# RfLauchPadAdapter.net
KiCad netlist of a schematic drawn in Altium Designer
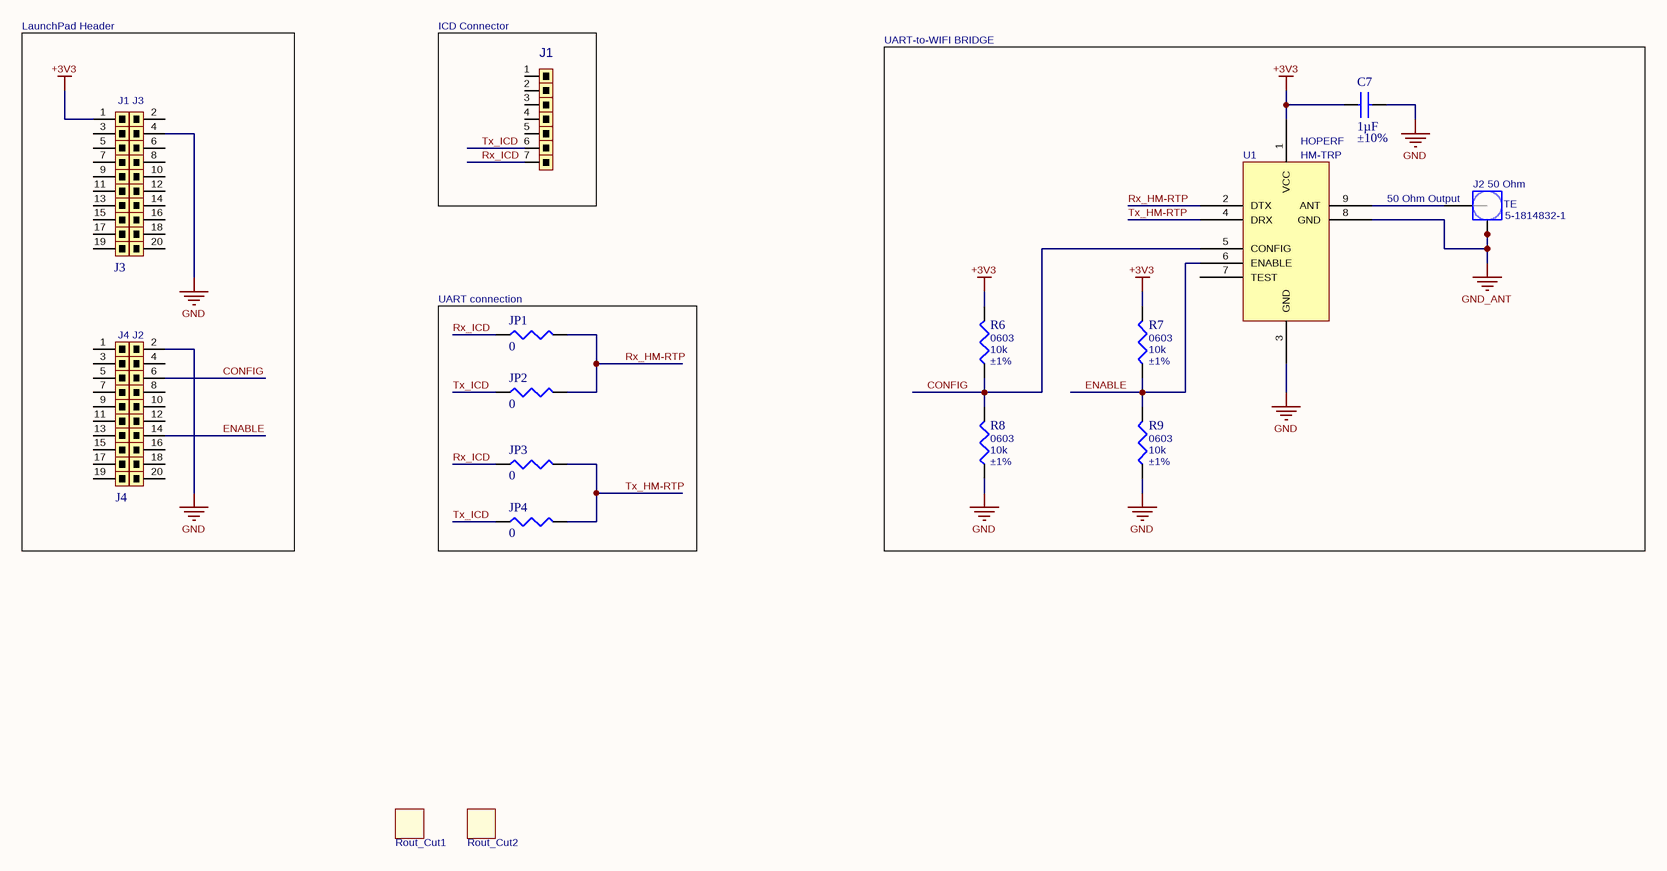
[diagram p0: RfLauchPadAdapter.SchDoc]

(export (version "E")
  (design (tool "Eeschema 10.0.6"))
  (components
    (comp (ref "C7")
      (value "GRM188R61C105KA93D")
      (footprint "C0603")
      (description "CAP CER 1UF 16V 10% X5R 0603")
      (fields
        (field (name "MANUFACTURER") "Murata Electronics North America")
        (field (name "CAPACITANCE") "1µF")
        (field (name "TOLERANCE") "±10%")
      )
      (libsource (lib "CAP") (part "GRM188R61C105KA93D"))
    )
    (comp (ref "J1")
      (value "Header 1x7")
      (footprint "Post Height Terminal Strip 1x7")
      (libsource (lib "CON_Standard") (part "Header 1x7"))
    )
    (comp (ref "J2")
      (value "5-1814832-1")
      (footprint "5-1814832-1")
      (description "CONN SMA JACK STR 50 OHM PCB")
      (fields (field (name "IMPEDANCE") "50 Ohm") (field (name "MANUFACTURER") "TE"))
      (libsource (lib "CON_TE") (part "5-1814832-1"))
    )
    (comp (ref "J3")
      (value "Header 2x10")
      (footprint "Post Height Terminal Strip 2x10")
      (libsource (lib "CON_Standard") (part "Header 2x10"))
    )
    (comp (ref "J4")
      (value "Header 2x10")
      (footprint "Post Height Terminal Strip 2x10")
      (libsource (lib "CON_Standard") (part "Header 2x10"))
    )
    (comp (ref "JP1")
      (value "ERJ-3GEY0R00V")
      (footprint "R0603")
      (description "0R JUMPER 1/10W")
      (fields
        (field (name "MANUFACTURER") "Panasonic Electronic Components")
        (field (name "RESISTANCE (OHMS)") "0")
      )
      (libsource (lib "RES") (part "ERJ-3GEY0R00V"))
    )
    (comp (ref "JP2")
      (value "ERJ-3GEY0R00V")
      (footprint "R0603")
      (description "0R JUMPER 1/10W")
      (fields
        (field (name "MANUFACTURER") "Panasonic Electronic Components")
        (field (name "RESISTANCE (OHMS)") "0")
      )
      (libsource (lib "RES") (part "ERJ-3GEY0R00V"))
    )
    (comp (ref "JP3")
      (value "ERJ-3GEY0R00V")
      (footprint "R0603")
      (description "0R JUMPER 1/10W")
      (fields
        (field (name "MANUFACTURER") "Panasonic Electronic Components")
        (field (name "RESISTANCE (OHMS)") "0")
      )
      (libsource (lib "RES") (part "ERJ-3GEY0R00V"))
    )
    (comp (ref "JP4")
      (value "ERJ-3GEY0R00V")
      (footprint "R0603")
      (description "0R JUMPER 1/10W")
      (fields
        (field (name "MANUFACTURER") "Panasonic Electronic Components")
        (field (name "RESISTANCE (OHMS)") "0")
      )
      (libsource (lib "RES") (part "ERJ-3GEY0R00V"))
    )
    (comp (ref "R6")
      (value "ERJ-3EKF1002V")
      (footprint "R0603")
      (description "10K OHM 1% 1/10W 0603")
      (fields
        (field (name "MANUFACTURER") "Panasonic Electronic Components")
        (field (name "SUPPLIER DEVICE PACKAGE") "0603")
        (field (name "RESISTANCE (OHMS)") "10k")
        (field (name "TOLERANCE") "±1%")
      )
      (libsource (lib "RES") (part "ERJ-3EKF1002V"))
    )
    (comp (ref "R7")
      (value "ERJ-3EKF1002V")
      (footprint "R0603")
      (description "10K OHM 1% 1/10W 0603")
      (fields
        (field (name "MANUFACTURER") "Panasonic Electronic Components")
        (field (name "SUPPLIER DEVICE PACKAGE") "0603")
        (field (name "RESISTANCE (OHMS)") "10k")
        (field (name "TOLERANCE") "±1%")
      )
      (libsource (lib "RES") (part "ERJ-3EKF1002V"))
    )
    (comp (ref "R8")
      (value "ERJ-3EKF1002V")
      (footprint "R0603")
      (description "10K OHM 1% 1/10W 0603")
      (fields
        (field (name "MANUFACTURER") "Panasonic Electronic Components")
        (field (name "SUPPLIER DEVICE PACKAGE") "0603")
        (field (name "RESISTANCE (OHMS)") "10k")
        (field (name "TOLERANCE") "±1%")
      )
      (libsource (lib "RES") (part "ERJ-3EKF1002V"))
    )
    (comp (ref "R9")
      (value "ERJ-3EKF1002V")
      (footprint "R0603")
      (description "10K OHM 1% 1/10W 0603")
      (fields
        (field (name "MANUFACTURER") "Panasonic Electronic Components")
        (field (name "SUPPLIER DEVICE PACKAGE") "0603")
        (field (name "RESISTANCE (OHMS)") "10k")
        (field (name "TOLERANCE") "±1%")
      )
      (libsource (lib "RES") (part "ERJ-3EKF1002V"))
    )
    (comp (ref "Rout_Cut1")
      (value "Rout_Cut")
      (footprint "RoutCut")
      (description "1.6mm")
      (libsource (lib "Misc") (part "Rout_Cut"))
    )
    (comp (ref "Rout_Cut2")
      (value "Rout_Cut")
      (footprint "RoutCut")
      (description "1.6mm")
      (libsource (lib "Misc") (part "Rout_Cut"))
    )
    (comp (ref "U1")
      (value "HM-TRP")
      (footprint "HM-TRP")
      (fields (field (name "MANUFACTURER") "HOPERF"))
      (libsource (lib "RF_HOPERF") (part "HM-TRP"))
    )
  )
  (nets
    (net (code "1") (name "+3V3") (class "Default")
      (node (ref "C7") (pin "1") (pinfunction "1_1") (pintype "passive"))
      (node (ref "J3") (pin "1") (pinfunction "1_1") (pintype "passive"))
      (node (ref "R6") (pin "2") (pinfunction "2_2") (pintype "passive"))
      (node (ref "R7") (pin "2") (pinfunction "2_2") (pintype "passive"))
      (node (ref "U1") (pin "1") (pinfunction "VCC_1") (pintype "passive"))
    )
    (net (code "2") (name "/CONFIG") (class "Default")
      (node (ref "J4") (pin "6") (pinfunction "6_6") (pintype "passive"))
      (node (ref "R6") (pin "1") (pinfunction "1_1") (pintype "passive"))
      (node (ref "R8") (pin "2") (pinfunction "2_2") (pintype "passive"))
      (node (ref "U1") (pin "5") (pinfunction "CONFIG_5") (pintype "passive"))
    )
    (net (code "3") (name "/ENABLE") (class "Default")
      (node (ref "J4") (pin "14") (pinfunction "14_14") (pintype "passive"))
      (node (ref "R7") (pin "1") (pinfunction "1_1") (pintype "passive"))
      (node (ref "R9") (pin "2") (pinfunction "2_2") (pintype "passive"))
      (node (ref "U1") (pin "6") (pinfunction "ENABLE_6") (pintype "passive"))
    )
    (net (code "4") (name "/Rx_HM-RTP") (class "Default")
      (node (ref "JP1") (pin "2") (pinfunction "2_2") (pintype "passive"))
      (node (ref "JP2") (pin "2") (pinfunction "2_2") (pintype "passive"))
      (node (ref "U1") (pin "2") (pinfunction "DTX_2") (pintype "passive"))
    )
    (net (code "5") (name "/Rx_ICD") (class "Default")
      (node (ref "J1") (pin "7") (pinfunction "7_7") (pintype "passive"))
      (node (ref "JP1") (pin "1") (pinfunction "1_1") (pintype "passive"))
      (node (ref "JP3") (pin "1") (pinfunction "1_1") (pintype "passive"))
    )
    (net (code "6") (name "/Tx_HM-RTP") (class "Default")
      (node (ref "JP3") (pin "2") (pinfunction "2_2") (pintype "passive"))
      (node (ref "JP4") (pin "2") (pinfunction "2_2") (pintype "passive"))
      (node (ref "U1") (pin "4") (pinfunction "DRX_4") (pintype "passive"))
    )
    (net (code "7") (name "/Tx_ICD") (class "Default")
      (node (ref "J1") (pin "6") (pinfunction "6_6") (pintype "passive"))
      (node (ref "JP2") (pin "1") (pinfunction "1_1") (pintype "passive"))
      (node (ref "JP4") (pin "1") (pinfunction "1_1") (pintype "passive"))
    )
    (net (code "8") (name "GND") (class "Default")
      (node (ref "C7") (pin "2") (pinfunction "2_2") (pintype "passive"))
      (node (ref "J3") (pin "4") (pinfunction "4_4") (pintype "passive"))
      (node (ref "J4") (pin "2") (pinfunction "2_2") (pintype "passive"))
      (node (ref "R8") (pin "1") (pinfunction "1_1") (pintype "passive"))
      (node (ref "R9") (pin "1") (pinfunction "1_1") (pintype "passive"))
      (node (ref "U1") (pin "3") (pinfunction "GND_3") (pintype "passive"))
    )
    (net (code "9") (name "GND_ANT") (class "Default")
      (node (ref "J2") (pin "2") (pinfunction "2_2") (pintype "passive"))
      (node (ref "J2") (pin "3") (pinfunction "3_3") (pintype "passive"))
      (node (ref "J2") (pin "4") (pinfunction "4_4") (pintype "passive"))
      (node (ref "J2") (pin "5") (pinfunction "5_5") (pintype "passive"))
      (node (ref "U1") (pin "8") (pinfunction "GND_8") (pintype "passive"))
    )
    (net (code "10") (name "Net-(U1-ANT)") (class "Default")
      (node (ref "J2") (pin "1") (pinfunction "1_1") (pintype "passive"))
      (node (ref "U1") (pin "9") (pinfunction "ANT_9") (pintype "passive"))
    )
    (net (code "11") (name "unconnected-(J1-Pad1)") (class "Default")
      (node (ref "J1") (pin "1") (pinfunction "1_1") (pintype "passive"))
    )
    (net (code "12") (name "unconnected-(J1-Pad2)") (class "Default")
      (node (ref "J1") (pin "2") (pinfunction "2_2") (pintype "passive"))
    )
    (net (code "13") (name "unconnected-(J1-Pad3)") (class "Default")
      (node (ref "J1") (pin "3") (pinfunction "3_3") (pintype "passive"))
    )
    (net (code "14") (name "unconnected-(J1-Pad4)") (class "Default")
      (node (ref "J1") (pin "4") (pinfunction "4_4") (pintype "passive"))
    )
    (net (code "15") (name "unconnected-(J1-Pad5)") (class "Default")
      (node (ref "J1") (pin "5") (pinfunction "5_5") (pintype "passive"))
    )
    (net (code "16") (name "unconnected-(J3-Pad2)") (class "Default")
      (node (ref "J3") (pin "2") (pinfunction "2_2") (pintype "passive"))
    )
    (net (code "17") (name "unconnected-(J3-Pad3)") (class "Default")
      (node (ref "J3") (pin "3") (pinfunction "3_3") (pintype "passive"))
    )
    (net (code "18") (name "unconnected-(J3-Pad5)") (class "Default")
      (node (ref "J3") (pin "5") (pinfunction "5_5") (pintype "passive"))
    )
    (net (code "19") (name "unconnected-(J3-Pad6)") (class "Default")
      (node (ref "J3") (pin "6") (pinfunction "6_6") (pintype "passive"))
    )
    (net (code "20") (name "unconnected-(J3-Pad7)") (class "Default")
      (node (ref "J3") (pin "7") (pinfunction "7_7") (pintype "passive"))
    )
    (net (code "21") (name "unconnected-(J3-Pad8)") (class "Default")
      (node (ref "J3") (pin "8") (pinfunction "8_8") (pintype "passive"))
    )
    (net (code "22") (name "unconnected-(J3-Pad9)") (class "Default")
      (node (ref "J3") (pin "9") (pinfunction "9_9") (pintype "passive"))
    )
    (net (code "23") (name "unconnected-(J3-Pad10)") (class "Default")
      (node (ref "J3") (pin "10") (pinfunction "10_10") (pintype "passive"))
    )
    (net (code "24") (name "unconnected-(J3-Pad11)") (class "Default")
      (node (ref "J3") (pin "11") (pinfunction "11_11") (pintype "passive"))
    )
    (net (code "25") (name "unconnected-(J3-Pad12)") (class "Default")
      (node (ref "J3") (pin "12") (pinfunction "12_12") (pintype "passive"))
    )
    (net (code "26") (name "unconnected-(J3-Pad13)") (class "Default")
      (node (ref "J3") (pin "13") (pinfunction "13_13") (pintype "passive"))
    )
    (net (code "27") (name "unconnected-(J3-Pad14)") (class "Default")
      (node (ref "J3") (pin "14") (pinfunction "14_14") (pintype "passive"))
    )
    (net (code "28") (name "unconnected-(J3-Pad15)") (class "Default")
      (node (ref "J3") (pin "15") (pinfunction "15_15") (pintype "passive"))
    )
    (net (code "29") (name "unconnected-(J3-Pad16)") (class "Default")
      (node (ref "J3") (pin "16") (pinfunction "16_16") (pintype "passive"))
    )
    (net (code "30") (name "unconnected-(J3-Pad17)") (class "Default")
      (node (ref "J3") (pin "17") (pinfunction "17_17") (pintype "passive"))
    )
    (net (code "31") (name "unconnected-(J3-Pad18)") (class "Default")
      (node (ref "J3") (pin "18") (pinfunction "18_18") (pintype "passive"))
    )
    (net (code "32") (name "unconnected-(J3-Pad19)") (class "Default")
      (node (ref "J3") (pin "19") (pinfunction "19_19") (pintype "passive"))
    )
    (net (code "33") (name "unconnected-(J3-Pad20)") (class "Default")
      (node (ref "J3") (pin "20") (pinfunction "20_20") (pintype "passive"))
    )
    (net (code "34") (name "unconnected-(J4-Pad1)") (class "Default")
      (node (ref "J4") (pin "1") (pinfunction "1_1") (pintype "passive"))
    )
    (net (code "35") (name "unconnected-(J4-Pad3)") (class "Default")
      (node (ref "J4") (pin "3") (pinfunction "3_3") (pintype "passive"))
    )
    (net (code "36") (name "unconnected-(J4-Pad4)") (class "Default")
      (node (ref "J4") (pin "4") (pinfunction "4_4") (pintype "passive"))
    )
    (net (code "37") (name "unconnected-(J4-Pad5)") (class "Default")
      (node (ref "J4") (pin "5") (pinfunction "5_5") (pintype "passive"))
    )
    (net (code "38") (name "unconnected-(J4-Pad7)") (class "Default")
      (node (ref "J4") (pin "7") (pinfunction "7_7") (pintype "passive"))
    )
    (net (code "39") (name "unconnected-(J4-Pad8)") (class "Default")
      (node (ref "J4") (pin "8") (pinfunction "8_8") (pintype "passive"))
    )
    (net (code "40") (name "unconnected-(J4-Pad9)") (class "Default")
      (node (ref "J4") (pin "9") (pinfunction "9_9") (pintype "passive"))
    )
    (net (code "41") (name "unconnected-(J4-Pad10)") (class "Default")
      (node (ref "J4") (pin "10") (pinfunction "10_10") (pintype "passive"))
    )
    (net (code "42") (name "unconnected-(J4-Pad11)") (class "Default")
      (node (ref "J4") (pin "11") (pinfunction "11_11") (pintype "passive"))
    )
    (net (code "43") (name "unconnected-(J4-Pad12)") (class "Default")
      (node (ref "J4") (pin "12") (pinfunction "12_12") (pintype "passive"))
    )
    (net (code "44") (name "unconnected-(J4-Pad13)") (class "Default")
      (node (ref "J4") (pin "13") (pinfunction "13_13") (pintype "passive"))
    )
    (net (code "45") (name "unconnected-(J4-Pad15)") (class "Default")
      (node (ref "J4") (pin "15") (pinfunction "15_15") (pintype "passive"))
    )
    (net (code "46") (name "unconnected-(J4-Pad16)") (class "Default")
      (node (ref "J4") (pin "16") (pinfunction "16_16") (pintype "passive"))
    )
    (net (code "47") (name "unconnected-(J4-Pad17)") (class "Default")
      (node (ref "J4") (pin "17") (pinfunction "17_17") (pintype "passive"))
    )
    (net (code "48") (name "unconnected-(J4-Pad18)") (class "Default")
      (node (ref "J4") (pin "18") (pinfunction "18_18") (pintype "passive"))
    )
    (net (code "49") (name "unconnected-(J4-Pad19)") (class "Default")
      (node (ref "J4") (pin "19") (pinfunction "19_19") (pintype "passive"))
    )
    (net (code "50") (name "unconnected-(J4-Pad20)") (class "Default")
      (node (ref "J4") (pin "20") (pinfunction "20_20") (pintype "passive"))
    )
    (net (code "51") (name "unconnected-(U1-TEST-Pad7)") (class "Default")
      (node (ref "U1") (pin "7") (pinfunction "TEST_7") (pintype "passive"))
    )
  )
)
